# RevA.net
KiCad netlist of a schematic drawn in EAGLE
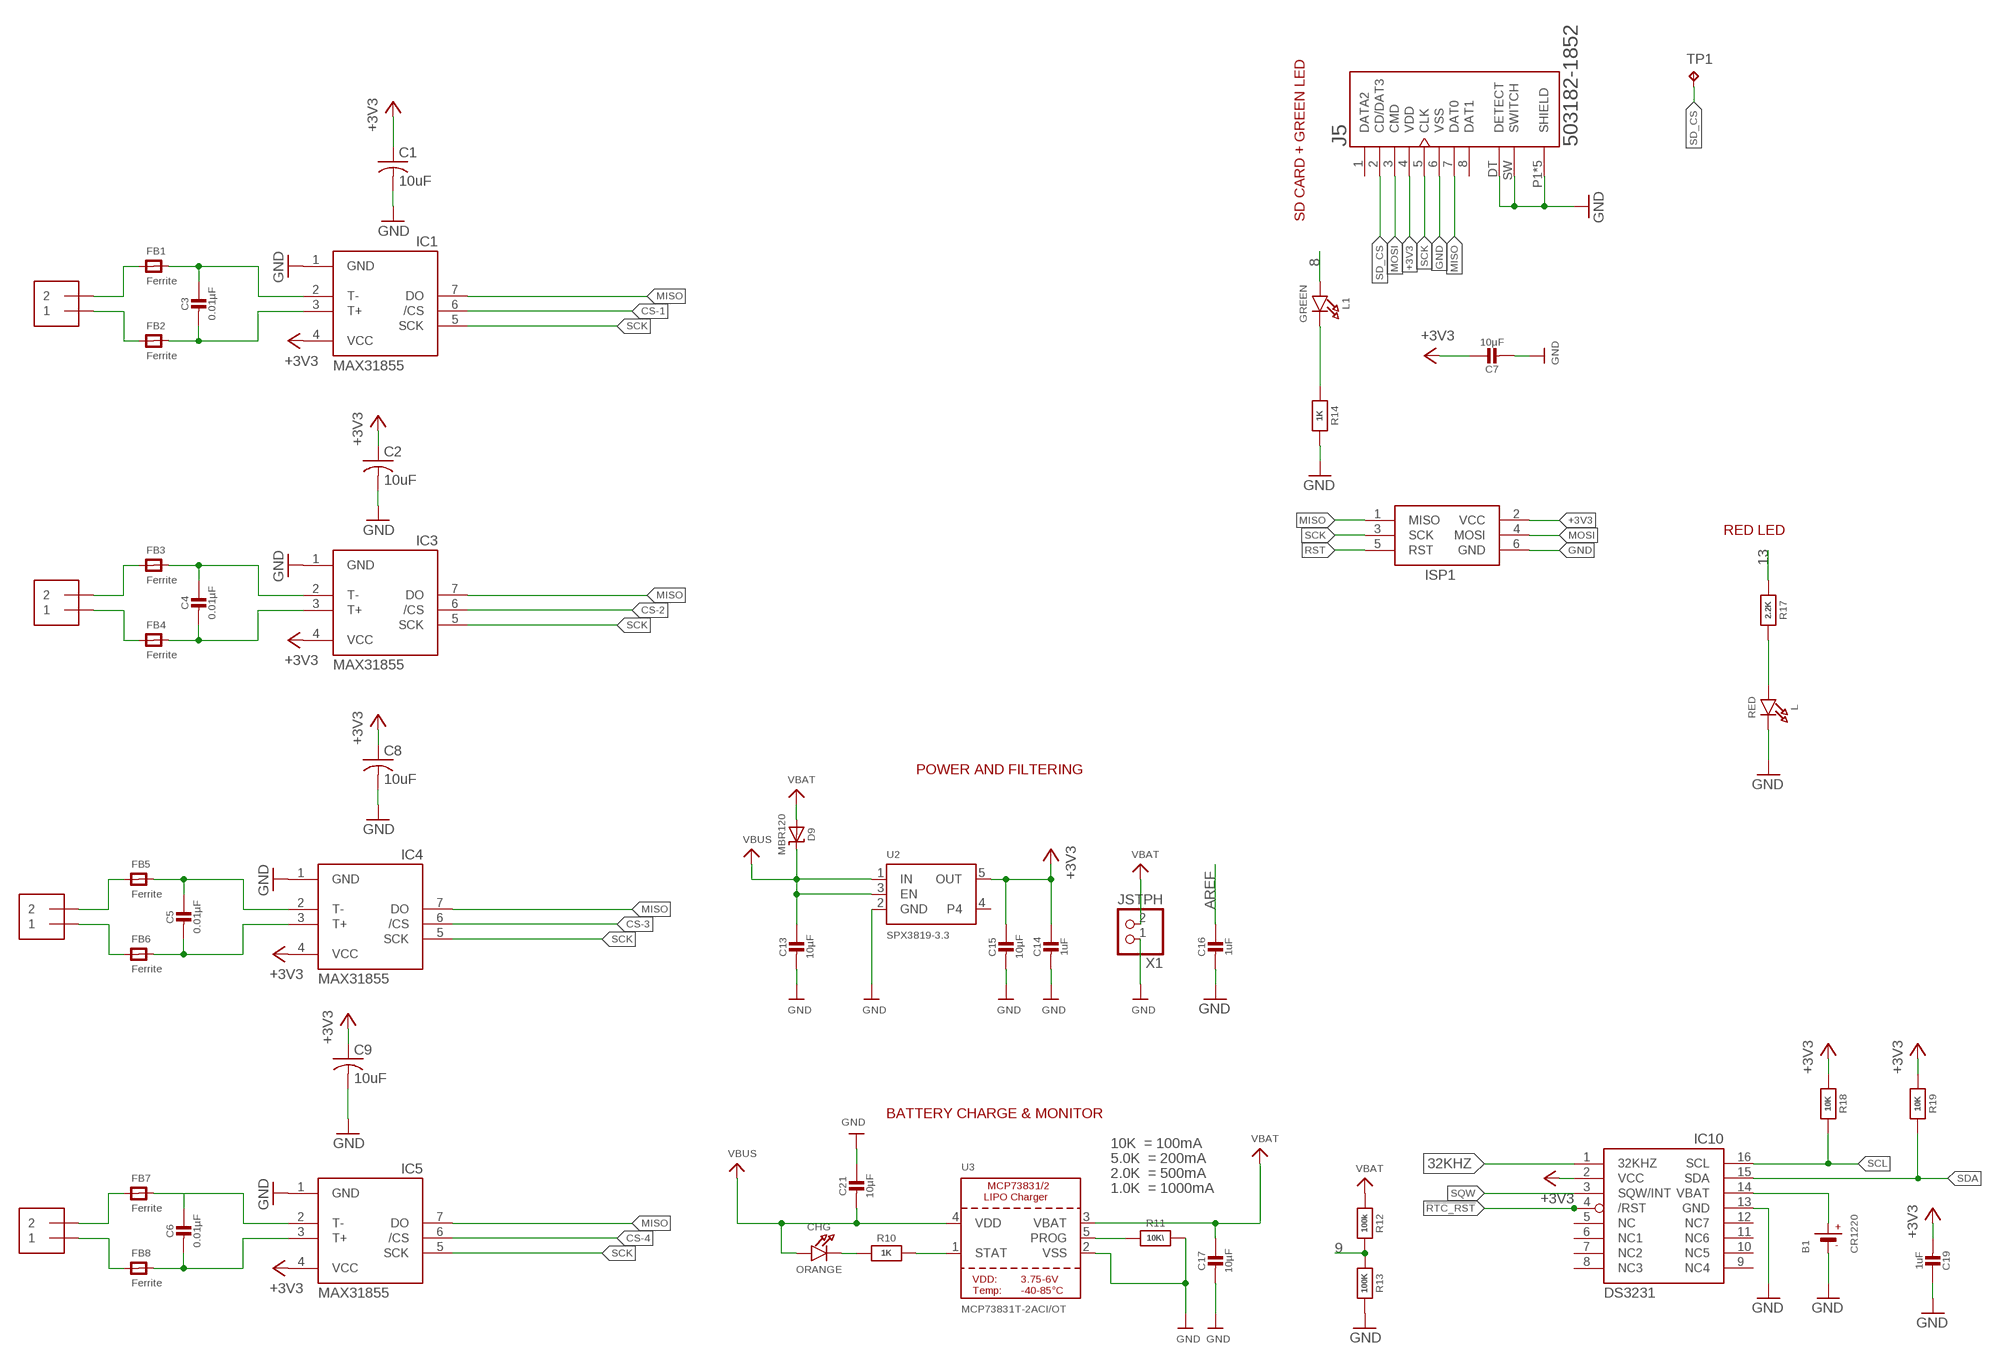
[diagram p0: schematic, sheet 1, part 1 of 2]
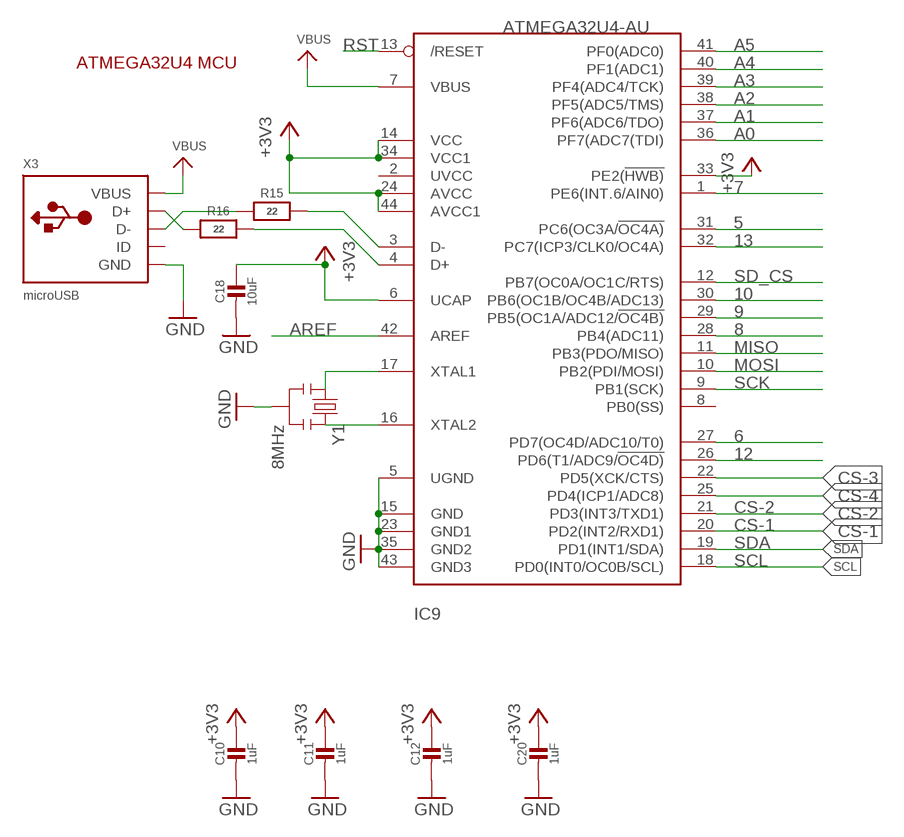
[diagram p1: schematic, sheet 1, part 2 of 2]

(export (version "E")
  (design (tool "Eeschema 10.0.6"))
  (components
    (comp (ref "B1")
      (value "CR1220")
      (footprint "eagle-import:CR1220")
      (libsource (lib "eagle-import") (part "BATTERYCR1220_SMT"))
    )
    (comp (ref "C1")
      (value "10uF")
      (footprint "eagle-import:C0805K")
      (libsource (lib "eagle-import") (part "C-USC0805K"))
    )
    (comp (ref "C2")
      (value "10uF")
      (footprint "eagle-import:C0805K")
      (libsource (lib "eagle-import") (part "C-USC0805K"))
    )
    (comp (ref "C3")
      (value "0.01µF")
      (footprint "eagle-import:_0805")
      (libsource (lib "eagle-import") (part "CAP_CERAMIC_0805"))
    )
    (comp (ref "C4")
      (value "0.01µF")
      (footprint "eagle-import:_0805")
      (libsource (lib "eagle-import") (part "CAP_CERAMIC_0805"))
    )
    (comp (ref "C5")
      (value "0.01µF")
      (footprint "eagle-import:_0805")
      (libsource (lib "eagle-import") (part "CAP_CERAMIC_0805"))
    )
    (comp (ref "C6")
      (value "0.01µF")
      (footprint "eagle-import:_0805")
      (libsource (lib "eagle-import") (part "CAP_CERAMIC_0805"))
    )
    (comp (ref "C7")
      (value "10µF")
      (footprint "eagle-import:0805-NO")
      (libsource (lib "eagle-import") (part "CAP_CERAMIC0805-NOOUTLINE"))
    )
    (comp (ref "C8")
      (value "10uF")
      (footprint "eagle-import:C0805K")
      (libsource (lib "eagle-import") (part "C-USC0805K"))
    )
    (comp (ref "C9")
      (value "10uF")
      (footprint "eagle-import:C0805K")
      (libsource (lib "eagle-import") (part "C-USC0805K"))
    )
    (comp (ref "C10")
      (value "1uF")
      (footprint "eagle-import:0603-NO")
      (libsource (lib "eagle-import") (part "CAP_CERAMIC0603_NO"))
    )
    (comp (ref "C11")
      (value "1uF")
      (footprint "eagle-import:0603-NO")
      (libsource (lib "eagle-import") (part "CAP_CERAMIC0603_NO"))
    )
    (comp (ref "C12")
      (value "1uF")
      (footprint "eagle-import:0603-NO")
      (libsource (lib "eagle-import") (part "CAP_CERAMIC0603_NO"))
    )
    (comp (ref "C13")
      (value "10µF")
      (footprint "eagle-import:0805-NO")
      (libsource (lib "eagle-import") (part "CAP_CERAMIC0805-NOOUTLINE"))
    )
    (comp (ref "C14")
      (value "1uF")
      (footprint "eagle-import:0603-NO")
      (libsource (lib "eagle-import") (part "CAP_CERAMIC0603_NO"))
    )
    (comp (ref "C15")
      (value "10µF")
      (footprint "eagle-import:0805-NO")
      (libsource (lib "eagle-import") (part "CAP_CERAMIC0805-NOOUTLINE"))
    )
    (comp (ref "C16")
      (value "1uF")
      (footprint "eagle-import:0603-NO")
      (libsource (lib "eagle-import") (part "CAP_CERAMIC0603_NO"))
    )
    (comp (ref "C17")
      (value "10µF")
      (footprint "eagle-import:0805-NO")
      (libsource (lib "eagle-import") (part "CAP_CERAMIC0805-NOOUTLINE"))
    )
    (comp (ref "C18")
      (value "10uF")
      (footprint "eagle-import:0805-NO")
      (libsource (lib "eagle-import") (part "CAP_CERAMIC0805-NOOUTLINE"))
    )
    (comp (ref "C19")
      (value "1uF")
      (footprint "eagle-import:0805-NO")
      (libsource (lib "eagle-import") (part "CAP_CERAMIC0805-NOOUTLINE"))
    )
    (comp (ref "C20")
      (value "1uF")
      (footprint "eagle-import:0603-NO")
      (libsource (lib "eagle-import") (part "CAP_CERAMIC0603_NO"))
    )
    (comp (ref "C21")
      (value "10µF")
      (footprint "eagle-import:0805-NO")
      (libsource (lib "eagle-import") (part "CAP_CERAMIC0805-NOOUTLINE"))
    )
    (comp (ref "CHG")
      (value "ORANGE")
      (footprint "eagle-import:CHIPLED_0805_NOOUTLINE")
      (libsource (lib "eagle-import") (part "LED0805_NOOUTLINE"))
    )
    (comp (ref "D9")
      (value "MBR120")
      (footprint "eagle-import:SOD-123")
      (libsource (lib "eagle-import") (part "DIODE-SCHOTTKYSOD-123"))
    )
    (comp (ref "FB1")
      (value "Ferrite")
      (footprint "eagle-import:_0805")
      (libsource (lib "eagle-import") (part "FERRITE_0805"))
    )
    (comp (ref "FB2")
      (value "Ferrite")
      (footprint "eagle-import:_0805")
      (libsource (lib "eagle-import") (part "FERRITE_0805"))
    )
    (comp (ref "FB3")
      (value "Ferrite")
      (footprint "eagle-import:_0805")
      (libsource (lib "eagle-import") (part "FERRITE_0805"))
    )
    (comp (ref "FB4")
      (value "Ferrite")
      (footprint "eagle-import:_0805")
      (libsource (lib "eagle-import") (part "FERRITE_0805"))
    )
    (comp (ref "FB5")
      (value "Ferrite")
      (footprint "eagle-import:_0805")
      (libsource (lib "eagle-import") (part "FERRITE_0805"))
    )
    (comp (ref "FB6")
      (value "Ferrite")
      (footprint "eagle-import:_0805")
      (libsource (lib "eagle-import") (part "FERRITE_0805"))
    )
    (comp (ref "FB7")
      (value "Ferrite")
      (footprint "eagle-import:_0805")
      (libsource (lib "eagle-import") (part "FERRITE_0805"))
    )
    (comp (ref "FB8")
      (value "Ferrite")
      (footprint "eagle-import:_0805")
      (libsource (lib "eagle-import") (part "FERRITE_0805"))
    )
    (comp (ref "IC1")
      (value "MAX31855")
      (footprint "eagle-import:SO08")
      (libsource (lib "eagle-import") (part "MAX6675"))
    )
    (comp (ref "IC3")
      (value "MAX31855")
      (footprint "eagle-import:SO08")
      (libsource (lib "eagle-import") (part "MAX6675"))
    )
    (comp (ref "IC4")
      (value "MAX31855")
      (footprint "eagle-import:SO08")
      (libsource (lib "eagle-import") (part "MAX6675"))
    )
    (comp (ref "IC5")
      (value "MAX31855")
      (footprint "eagle-import:SO08")
      (libsource (lib "eagle-import") (part "MAX6675"))
    )
    (comp (ref "IC9")
      (value "ATMEGA32U4-AU")
      (footprint "eagle-import:TQFP44")
      (libsource (lib "eagle-import") (part "ATMEGA32U4-AU"))
    )
    (comp (ref "IC10")
      (value "DS3231/SO")
      (footprint "eagle-import:SO16W")
      (libsource (lib "eagle-import") (part "DS3231/SO"))
    )
    (comp (ref "ISP1")
      (value "AVRISP-BOX")
      (footprint "eagle-import:AVRISP-BOX")
      (libsource (lib "eagle-import") (part "AVRISP-BOX"))
    )
    (comp (ref "J1")
      (value "1X2-3.5MM")
      (footprint "eagle-import:1X2-3.5MM")
      (libsource (lib "eagle-import") (part "1X2-3.5MM"))
    )
    (comp (ref "J2")
      (value "1X2-3.5MM")
      (footprint "eagle-import:1X2-3.5MM")
      (libsource (lib "eagle-import") (part "1X2-3.5MM"))
    )
    (comp (ref "J3")
      (value "1X2-3.5MM")
      (footprint "eagle-import:1X2-3.5MM")
      (libsource (lib "eagle-import") (part "1X2-3.5MM"))
    )
    (comp (ref "J4")
      (value "1X2-3.5MM")
      (footprint "eagle-import:1X2-3.5MM")
      (libsource (lib "eagle-import") (part "1X2-3.5MM"))
    )
    (comp (ref "J5")
      (value "503182-1852")
      (footprint "eagle-import:MOLEX_503182-1852")
      (fields
        (field (name "DIGI-KEY_PART_NUMBER") "WM12834CT-ND")
        (field (name "MF") "Molex")
        (field (name "MP") "5031821852")
      )
      (libsource (lib "eagle-import") (part "503182-1852"))
    )
    (comp (ref "L")
      (value "RED")
      (footprint "eagle-import:CHIPLED_0805_NOOUTLINE")
      (libsource (lib "eagle-import") (part "LED0805_NOOUTLINE"))
    )
    (comp (ref "L1")
      (value "GREEN")
      (footprint "eagle-import:CHIPLED_0805_NOOUTLINE")
      (libsource (lib "eagle-import") (part "LED0805_NOOUTLINE"))
    )
    (comp (ref "R10")
      (value "1K")
      (footprint "eagle-import:0603-NO")
      (libsource (lib "eagle-import") (part "RESISTOR_0603_NOOUT"))
    )
    (comp (ref "R11")
      (value "10K\\")
      (footprint "eagle-import:0603-NO")
      (libsource (lib "eagle-import") (part "RESISTOR_0603_NOOUT"))
    )
    (comp (ref "R12")
      (value "100k")
      (footprint "eagle-import:_0603MP")
      (libsource (lib "eagle-import") (part "RESISTOR_0603MP"))
    )
    (comp (ref "R13")
      (value "100K")
      (footprint "eagle-import:_0603MP")
      (libsource (lib "eagle-import") (part "RESISTOR_0603MP"))
    )
    (comp (ref "R14")
      (value "1K")
      (footprint "eagle-import:0603-NO")
      (libsource (lib "eagle-import") (part "RESISTOR_0603_NOOUT"))
    )
    (comp (ref "R15")
      (value "22")
      (footprint "eagle-import:0603-NO")
      (libsource (lib "eagle-import") (part "RESISTOR_0603_NOOUT"))
    )
    (comp (ref "R16")
      (value "22")
      (footprint "eagle-import:0603-NO")
      (libsource (lib "eagle-import") (part "RESISTOR_0603_NOOUT"))
    )
    (comp (ref "R17")
      (value "2.2K")
      (footprint "eagle-import:0603-NO")
      (libsource (lib "eagle-import") (part "RESISTOR_0603_NOOUT"))
    )
    (comp (ref "R18")
      (value "10K")
      (footprint "eagle-import:0805-NO")
      (libsource (lib "eagle-import") (part "RESISTOR0805_NOOUTLINE"))
    )
    (comp (ref "R19")
      (value "10K")
      (footprint "eagle-import:0805-NO")
      (libsource (lib "eagle-import") (part "RESISTOR0805_NOOUTLINE"))
    )
    (comp (ref "TP1")
      (value "TPPAD1-13")
      (footprint "eagle-import:P1-13")
      (libsource (lib "eagle-import") (part "TPPAD1-13"))
    )
    (comp (ref "U2")
      (value "SPX3819-3.3")
      (footprint "eagle-import:SOT23-5")
      (libsource (lib "eagle-import") (part "VREG_SOT23-5"))
    )
    (comp (ref "U3")
      (value "MCP73831T-2ACI/OT")
      (footprint "eagle-import:SOT23-5")
      (libsource (lib "eagle-import") (part "MCP73831/2"))
    )
    (comp (ref "X1")
      (value "JSTPH")
      (footprint "eagle-import:JSTPH2")
      (libsource (lib "eagle-import") (part "CON_JST_PH_2PIN"))
    )
    (comp (ref "X3")
      (value "microUSB")
      (footprint "eagle-import:4UCONN_20329_V2")
      (libsource (lib "eagle-import") (part "USB_MICRO_20329_V2"))
    )
    (comp (ref "Y1")
      (value "8MHz")
      (footprint "eagle-import:RESONATOR-SMD")
      (libsource (lib "eagle-import") (part "RESONATORSMD"))
    )
  )
  (nets
    (net (code "1") (name "+3V3") (class "Default")
      (node (ref "C1") (pin "1") (pinfunction "1_1") (pintype "passive"))
      (node (ref "C10") (pin "1") (pinfunction "1_1") (pintype "passive"))
      (node (ref "C11") (pin "1") (pinfunction "1_1") (pintype "passive"))
      (node (ref "C12") (pin "1") (pinfunction "1_1") (pintype "passive"))
      (node (ref "C14") (pin "1") (pinfunction "1_1") (pintype "passive"))
      (node (ref "C15") (pin "1") (pinfunction "1_1") (pintype "passive"))
      (node (ref "C18") (pin "1") (pinfunction "1_1") (pintype "passive"))
      (node (ref "C19") (pin "2") (pinfunction "2_2") (pintype "passive"))
      (node (ref "C2") (pin "1") (pinfunction "1_1") (pintype "passive"))
      (node (ref "C20") (pin "1") (pinfunction "1_1") (pintype "passive"))
      (node (ref "C7") (pin "1") (pinfunction "1_1") (pintype "passive"))
      (node (ref "C8") (pin "1") (pinfunction "1_1") (pintype "passive"))
      (node (ref "C9") (pin "1") (pinfunction "1_1") (pintype "passive"))
      (node (ref "IC1") (pin "4") (pinfunction "VCC_4") (pintype "power_in"))
      (node (ref "IC10") (pin "2") (pinfunction "VCC_2") (pintype "power_in"))
      (node (ref "IC3") (pin "4") (pinfunction "VCC_4") (pintype "power_in"))
      (node (ref "IC4") (pin "4") (pinfunction "VCC_4") (pintype "power_in"))
      (node (ref "IC5") (pin "4") (pinfunction "VCC_4") (pintype "power_in"))
      (node (ref "IC9") (pin "14") (pinfunction "VCC_14") (pintype "bidirectional"))
      (node (ref "IC9") (pin "24") (pinfunction "AVCC_24") (pintype "bidirectional"))
      (node (ref "IC9") (pin "33") (pinfunction "PE2(~{HWB})_33") (pintype "bidirectional"))
      (node (ref "IC9") (pin "34") (pinfunction "VCC1_34") (pintype "bidirectional"))
      (node (ref "IC9") (pin "44") (pinfunction "AVCC1_44") (pintype "bidirectional"))
      (node (ref "IC9") (pin "6") (pinfunction "UCAP_6") (pintype "bidirectional"))
      (node (ref "ISP1") (pin "2") (pinfunction "VCC_2") (pintype "power_in"))
      (node (ref "J5") (pin "4") (pinfunction "VDD_4") (pintype "power_in"))
      (node (ref "R18") (pin "1") (pinfunction "1_1") (pintype "passive"))
      (node (ref "R19") (pin "1") (pinfunction "1_1") (pintype "passive"))
      (node (ref "U2") (pin "5") (pinfunction "OUT_5") (pintype "power_in"))
    )
    (net (code "2") (name "/5") (class "Default")
      (node (ref "IC9") (pin "31") (pinfunction "PC6(OC3A/~{OC4A})_31") (pintype "bidirectional"))
    )
    (net (code "3") (name "/6") (class "Default")
      (node (ref "IC9") (pin "27") (pinfunction "PD7(OC4D/ADC10/T0)_27") (pintype "bidirectional"))
    )
    (net (code "4") (name "/7") (class "Default")
      (node (ref "IC9") (pin "1") (pinfunction "PE6(INT.6/AIN0)_1") (pintype "bidirectional"))
    )
    (net (code "5") (name "/8") (class "Default")
      (node (ref "IC9") (pin "28") (pinfunction "PB4(ADC11)_28") (pintype "bidirectional"))
      (node (ref "L1") (pin "A") (pinfunction "A_A") (pintype "passive"))
    )
    (net (code "6") (name "/9") (class "Default")
      (node (ref "IC9") (pin "29") (pinfunction "PB5(OC1A/ADC12/~{OC4B})_29") (pintype "bidirectional"))
      (node (ref "R12") (pin "2") (pinfunction "2_2") (pintype "passive"))
      (node (ref "R13") (pin "1") (pinfunction "1_1") (pintype "passive"))
    )
    (net (code "7") (name "/10") (class "Default")
      (node (ref "IC9") (pin "30") (pinfunction "PB6(OC1B/OC4B/ADC13)_30") (pintype "bidirectional"))
    )
    (net (code "8") (name "/12") (class "Default")
      (node (ref "IC9") (pin "26") (pinfunction "PD6(T1/ADC9/~{OC4D})_26") (pintype "bidirectional"))
    )
    (net (code "9") (name "/13") (class "Default")
      (node (ref "IC9") (pin "32") (pinfunction "PC7(ICP3/CLK0/OC4A)_32") (pintype "bidirectional"))
      (node (ref "R17") (pin "1") (pinfunction "1_1") (pintype "passive"))
    )
    (net (code "10") (name "/A0") (class "Default")
      (node (ref "IC9") (pin "36") (pinfunction "PF7(ADC7(TDI)_36") (pintype "bidirectional"))
    )
    (net (code "11") (name "/A1") (class "Default")
      (node (ref "IC9") (pin "37") (pinfunction "PF6(ADC6/TDO)_37") (pintype "bidirectional"))
    )
    (net (code "12") (name "/A2") (class "Default")
      (node (ref "IC9") (pin "38") (pinfunction "PF5(ADC5/TMS)_38") (pintype "bidirectional"))
    )
    (net (code "13") (name "/A3") (class "Default")
      (node (ref "IC9") (pin "39") (pinfunction "PF4(ADC4/TCK)_39") (pintype "bidirectional"))
    )
    (net (code "14") (name "/A4") (class "Default")
      (node (ref "IC9") (pin "40") (pinfunction "PF1(ADC1)_40") (pintype "bidirectional"))
    )
    (net (code "15") (name "/A5") (class "Default")
      (node (ref "IC9") (pin "41") (pinfunction "PF0(ADC0)_41") (pintype "bidirectional"))
    )
    (net (code "16") (name "/AREF") (class "Default")
      (node (ref "C16") (pin "1") (pinfunction "1_1") (pintype "passive"))
      (node (ref "IC9") (pin "42") (pinfunction "AREF_42") (pintype "bidirectional"))
    )
    (net (code "17") (name "/~{RTC_RST}") (class "Default")
      (node (ref "IC10") (pin "4") (pinfunction "/RST_4") (pintype "passive"))
    )
    (net (code "18") (name "32KHZ") (class "Default")
      (node (ref "IC10") (pin "1") (pinfunction "32KHZ_1") (pintype "output"))
    )
    (net (code "19") (name "CS-1") (class "Default")
      (node (ref "IC1") (pin "6") (pinfunction "/CS_6") (pintype "input"))
      (node (ref "IC9") (pin "20") (pinfunction "PD2(INT2/RXD1)_20") (pintype "bidirectional"))
    )
    (net (code "20") (name "CS-2") (class "Default")
      (node (ref "IC3") (pin "6") (pinfunction "/CS_6") (pintype "input"))
      (node (ref "IC9") (pin "21") (pinfunction "PD3(INT3/TXD1)_21") (pintype "bidirectional"))
    )
    (net (code "21") (name "CS-3") (class "Default")
      (node (ref "IC4") (pin "6") (pinfunction "/CS_6") (pintype "input"))
      (node (ref "IC9") (pin "22") (pinfunction "PD5(XCK/CTS)_22") (pintype "bidirectional"))
    )
    (net (code "22") (name "CS-4") (class "Default")
      (node (ref "IC5") (pin "6") (pinfunction "/CS_6") (pintype "input"))
      (node (ref "IC9") (pin "25") (pinfunction "PD4(ICP1/ADC8)_25") (pintype "bidirectional"))
    )
    (net (code "23") (name "GND") (class "Default")
      (node (ref "B1") (pin "-") (pinfunction "-_-") (pintype "passive"))
      (node (ref "C1") (pin "2") (pinfunction "2_2") (pintype "passive"))
      (node (ref "C10") (pin "2") (pinfunction "2_2") (pintype "passive"))
      (node (ref "C11") (pin "2") (pinfunction "2_2") (pintype "passive"))
      (node (ref "C12") (pin "2") (pinfunction "2_2") (pintype "passive"))
      (node (ref "C13") (pin "2") (pinfunction "2_2") (pintype "passive"))
      (node (ref "C14") (pin "2") (pinfunction "2_2") (pintype "passive"))
      (node (ref "C15") (pin "2") (pinfunction "2_2") (pintype "passive"))
      (node (ref "C16") (pin "2") (pinfunction "2_2") (pintype "passive"))
      (node (ref "C17") (pin "2") (pinfunction "2_2") (pintype "passive"))
      (node (ref "C18") (pin "2") (pinfunction "2_2") (pintype "passive"))
      (node (ref "C19") (pin "1") (pinfunction "1_1") (pintype "passive"))
      (node (ref "C2") (pin "2") (pinfunction "2_2") (pintype "passive"))
      (node (ref "C20") (pin "2") (pinfunction "2_2") (pintype "passive"))
      (node (ref "C21") (pin "1") (pinfunction "1_1") (pintype "passive"))
      (node (ref "C7") (pin "2") (pinfunction "2_2") (pintype "passive"))
      (node (ref "C8") (pin "2") (pinfunction "2_2") (pintype "passive"))
      (node (ref "C9") (pin "2") (pinfunction "2_2") (pintype "passive"))
      (node (ref "IC1") (pin "1") (pinfunction "GND_1") (pintype "power_in"))
      (node (ref "IC10") (pin "13") (pinfunction "GND_13") (pintype "power_in"))
      (node (ref "IC3") (pin "1") (pinfunction "GND_1") (pintype "power_in"))
      (node (ref "IC4") (pin "1") (pinfunction "GND_1") (pintype "power_in"))
      (node (ref "IC5") (pin "1") (pinfunction "GND_1") (pintype "power_in"))
      (node (ref "IC9") (pin "15") (pinfunction "GND_15") (pintype "bidirectional"))
      (node (ref "IC9") (pin "23") (pinfunction "GND1_23") (pintype "bidirectional"))
      (node (ref "IC9") (pin "35") (pinfunction "GND2_35") (pintype "bidirectional"))
      (node (ref "IC9") (pin "43") (pinfunction "GND3_43") (pintype "bidirectional"))
      (node (ref "IC9") (pin "5") (pinfunction "UGND_5") (pintype "bidirectional"))
      (node (ref "ISP1") (pin "6") (pinfunction "GND_6") (pintype "power_in"))
      (node (ref "J5") (pin "6") (pinfunction "VSS_6") (pintype "power_in"))
      (node (ref "J5") (pin "DT") (pinfunction "DETECT_DT") (pintype "bidirectional"))
      (node (ref "J5") (pin "P1") (pinfunction "SHIELD_P1") (pintype "passive"))
      (node (ref "J5") (pin "P2") (pinfunction "SHIELD_P2") (pintype "passive"))
      (node (ref "J5") (pin "P3") (pinfunction "SHIELD_P3") (pintype "passive"))
      (node (ref "J5") (pin "P4") (pinfunction "SHIELD_P4") (pintype "passive"))
      (node (ref "J5") (pin "P5") (pinfunction "SHIELD_P5") (pintype "passive"))
      (node (ref "J5") (pin "SW") (pinfunction "SWITCH_SW") (pintype "bidirectional"))
      (node (ref "L") (pin "C") (pinfunction "C_C") (pintype "passive"))
      (node (ref "R11") (pin "2") (pinfunction "2_2") (pintype "passive"))
      (node (ref "R13") (pin "2") (pinfunction "2_2") (pintype "passive"))
      (node (ref "R14") (pin "2") (pinfunction "2_2") (pintype "passive"))
      (node (ref "U2") (pin "2") (pinfunction "GND_2") (pintype "power_in"))
      (node (ref "U3") (pin "2") (pinfunction "VSS_2") (pintype "power_in"))
      (node (ref "X1") (pin "1") (pinfunction "1_1") (pintype "passive"))
      (node (ref "X3") (pin "BASE@1") (pinfunction "GND_BASE@1") (pintype "power_in"))
      (node (ref "X3") (pin "BASE@2") (pinfunction "GND_BASE@2") (pintype "power_in"))
      (node (ref "X3") (pin "GND") (pinfunction "GND_GND") (pintype "power_in"))
      (node (ref "X3") (pin "SPRT@1") (pinfunction "GND_SPRT@1") (pintype "power_in"))
      (node (ref "X3") (pin "SPRT@2") (pinfunction "GND_SPRT@2") (pintype "power_in"))
      (node (ref "X3") (pin "SPRT@3") (pinfunction "GND_SPRT@3") (pintype "power_in"))
      (node (ref "X3") (pin "SPRT@4") (pinfunction "GND_SPRT@4") (pintype "power_in"))
      (node (ref "Y1") (pin "2") (pinfunction "2_2") (pintype "passive"))
    )
    (net (code "24") (name "MISO") (class "Default")
      (node (ref "IC1") (pin "7") (pinfunction "DO_7") (pintype "output"))
      (node (ref "IC3") (pin "7") (pinfunction "DO_7") (pintype "output"))
      (node (ref "IC4") (pin "7") (pinfunction "DO_7") (pintype "output"))
      (node (ref "IC5") (pin "7") (pinfunction "DO_7") (pintype "output"))
      (node (ref "IC9") (pin "11") (pinfunction "PB3(PDO/MISO)_11") (pintype "bidirectional"))
      (node (ref "ISP1") (pin "1") (pinfunction "MISO_1") (pintype "input"))
      (node (ref "J5") (pin "7") (pinfunction "DAT0_7") (pintype "bidirectional"))
    )
    (net (code "25") (name "MOSI") (class "Default")
      (node (ref "IC9") (pin "10") (pinfunction "PB2(PDI/MOSI)_10") (pintype "bidirectional"))
      (node (ref "ISP1") (pin "4") (pinfunction "MOSI_4") (pintype "output"))
      (node (ref "J5") (pin "3") (pinfunction "CMD_3") (pintype "bidirectional"))
    )
    (net (code "26") (name "Net-(B1-+)") (class "Default")
      (node (ref "B1") (pin "+$1") (pinfunction "+_+$1") (pintype "passive"))
      (node (ref "IC10") (pin "14") (pinfunction "VBAT_14") (pintype "power_in"))
    )
    (net (code "27") (name "Net-(CHG-PadC)") (class "Default")
      (node (ref "CHG") (pin "C") (pinfunction "C_C") (pintype "passive"))
      (node (ref "R10") (pin "1") (pinfunction "1_1") (pintype "passive"))
    )
    (net (code "28") (name "Net-(FB1-P$1)") (class "Default")
      (node (ref "FB1") (pin "1") (pinfunction "P$1_1") (pintype "passive"))
      (node (ref "J1") (pin "2") (pinfunction "2_2") (pintype "passive"))
    )
    (net (code "29") (name "Net-(FB1-P$2)") (class "Default")
      (node (ref "C3") (pin "1") (pinfunction "1_1") (pintype "passive"))
      (node (ref "FB1") (pin "2") (pinfunction "P$2_2") (pintype "passive"))
      (node (ref "IC1") (pin "2") (pinfunction "T-_2") (pintype "input"))
    )
    (net (code "30") (name "Net-(FB2-P$1)") (class "Default")
      (node (ref "FB2") (pin "1") (pinfunction "P$1_1") (pintype "passive"))
      (node (ref "J1") (pin "1") (pinfunction "1_1") (pintype "passive"))
    )
    (net (code "31") (name "Net-(FB2-P$2)") (class "Default")
      (node (ref "C3") (pin "2") (pinfunction "2_2") (pintype "passive"))
      (node (ref "FB2") (pin "2") (pinfunction "P$2_2") (pintype "passive"))
      (node (ref "IC1") (pin "3") (pinfunction "T+_3") (pintype "input"))
    )
    (net (code "32") (name "Net-(FB3-P$1)") (class "Default")
      (node (ref "FB3") (pin "1") (pinfunction "P$1_1") (pintype "passive"))
      (node (ref "J2") (pin "2") (pinfunction "2_2") (pintype "passive"))
    )
    (net (code "33") (name "Net-(FB3-P$2)") (class "Default")
      (node (ref "C4") (pin "1") (pinfunction "1_1") (pintype "passive"))
      (node (ref "FB3") (pin "2") (pinfunction "P$2_2") (pintype "passive"))
      (node (ref "IC3") (pin "2") (pinfunction "T-_2") (pintype "input"))
    )
    (net (code "34") (name "Net-(FB4-P$1)") (class "Default")
      (node (ref "FB4") (pin "1") (pinfunction "P$1_1") (pintype "passive"))
      (node (ref "J2") (pin "1") (pinfunction "1_1") (pintype "passive"))
    )
    (net (code "35") (name "Net-(FB4-P$2)") (class "Default")
      (node (ref "C4") (pin "2") (pinfunction "2_2") (pintype "passive"))
      (node (ref "FB4") (pin "2") (pinfunction "P$2_2") (pintype "passive"))
      (node (ref "IC3") (pin "3") (pinfunction "T+_3") (pintype "input"))
    )
    (net (code "36") (name "Net-(FB5-P$1)") (class "Default")
      (node (ref "FB5") (pin "1") (pinfunction "P$1_1") (pintype "passive"))
      (node (ref "J3") (pin "2") (pinfunction "2_2") (pintype "passive"))
    )
    (net (code "37") (name "Net-(FB5-P$2)") (class "Default")
      (node (ref "C5") (pin "1") (pinfunction "1_1") (pintype "passive"))
      (node (ref "FB5") (pin "2") (pinfunction "P$2_2") (pintype "passive"))
      (node (ref "IC4") (pin "2") (pinfunction "T-_2") (pintype "input"))
    )
    (net (code "38") (name "Net-(FB6-P$1)") (class "Default")
      (node (ref "FB6") (pin "1") (pinfunction "P$1_1") (pintype "passive"))
      (node (ref "J3") (pin "1") (pinfunction "1_1") (pintype "passive"))
    )
    (net (code "39") (name "Net-(FB6-P$2)") (class "Default")
      (node (ref "C5") (pin "2") (pinfunction "2_2") (pintype "passive"))
      (node (ref "FB6") (pin "2") (pinfunction "P$2_2") (pintype "passive"))
      (node (ref "IC4") (pin "3") (pinfunction "T+_3") (pintype "input"))
    )
    (net (code "40") (name "Net-(FB7-P$1)") (class "Default")
      (node (ref "FB7") (pin "1") (pinfunction "P$1_1") (pintype "passive"))
      (node (ref "J4") (pin "2") (pinfunction "2_2") (pintype "passive"))
    )
    (net (code "41") (name "Net-(FB7-P$2)") (class "Default")
      (node (ref "C6") (pin "1") (pinfunction "1_1") (pintype "passive"))
      (node (ref "FB7") (pin "2") (pinfunction "P$2_2") (pintype "passive"))
      (node (ref "IC5") (pin "2") (pinfunction "T-_2") (pintype "input"))
    )
    (net (code "42") (name "Net-(FB8-P$1)") (class "Default")
      (node (ref "FB8") (pin "1") (pinfunction "P$1_1") (pintype "passive"))
      (node (ref "J4") (pin "1") (pinfunction "1_1") (pintype "passive"))
    )
    (net (code "43") (name "Net-(FB8-P$2)") (class "Default")
      (node (ref "C6") (pin "2") (pinfunction "2_2") (pintype "passive"))
      (node (ref "FB8") (pin "2") (pinfunction "P$2_2") (pintype "passive"))
      (node (ref "IC5") (pin "3") (pinfunction "T+_3") (pintype "input"))
    )
    (net (code "44") (name "Net-(IC9-D+)") (class "Default")
      (node (ref "IC9") (pin "4") (pinfunction "D+_4") (pintype "bidirectional"))
      (node (ref "R16") (pin "2") (pinfunction "2_2") (pintype "passive"))
    )
    (net (code "45") (name "Net-(IC9-D-)") (class "Default")
      (node (ref "IC9") (pin "3") (pinfunction "D-_3") (pintype "bidirectional"))
      (node (ref "R15") (pin "2") (pinfunction "2_2") (pintype "passive"))
    )
    (net (code "46") (name "Net-(IC9-XTAL1)") (class "Default")
      (node (ref "IC9") (pin "17") (pinfunction "XTAL1_17") (pintype "bidirectional"))
      (node (ref "Y1") (pin "1") (pinfunction "1_1") (pintype "passive"))
    )
    (net (code "47") (name "Net-(IC9-XTAL2)") (class "Default")
      (node (ref "IC9") (pin "16") (pinfunction "XTAL2_16") (pintype "bidirectional"))
      (node (ref "Y1") (pin "3") (pinfunction "3_3") (pintype "passive"))
    )
    (net (code "48") (name "Net-(L-PadA)") (class "Default")
      (node (ref "L") (pin "A") (pinfunction "A_A") (pintype "passive"))
      (node (ref "R17") (pin "2") (pinfunction "2_2") (pintype "passive"))
    )
    (net (code "49") (name "Net-(L1-PadC)") (class "Default")
      (node (ref "L1") (pin "C") (pinfunction "C_C") (pintype "passive"))
      (node (ref "R14") (pin "1") (pinfunction "1_1") (pintype "passive"))
    )
    (net (code "50") (name "Net-(R15-Pad1)") (class "Default")
      (node (ref "R15") (pin "1") (pinfunction "1_1") (pintype "passive"))
      (node (ref "X3") (pin "D-") (pinfunction "D-_D-") (pintype "bidirectional"))
    )
    (net (code "51") (name "Net-(R16-Pad1)") (class "Default")
      (node (ref "R16") (pin "1") (pinfunction "1_1") (pintype "passive"))
      (node (ref "X3") (pin "D+") (pinfunction "D+_D+") (pintype "bidirectional"))
    )
    (net (code "52") (name "Net-(U3-PROG)") (class "Default")
      (node (ref "R11") (pin "1") (pinfunction "1_1") (pintype "passive"))
      (node (ref "U3") (pin "5") (pinfunction "PROG_5") (pintype "input"))
    )
    (net (code "53") (name "Net-(U3-STAT)") (class "Default")
      (node (ref "R10") (pin "2") (pinfunction "2_2") (pintype "passive"))
      (node (ref "U3") (pin "1") (pinfunction "STAT_1") (pintype "output"))
    )
    (net (code "54") (name "RST") (class "Default")
      (node (ref "IC9") (pin "13") (pinfunction "/RESET_13") (pintype "bidirectional"))
      (node (ref "ISP1") (pin "5") (pinfunction "RST_5") (pintype "output"))
    )
    (net (code "55") (name "SCK") (class "Default")
      (node (ref "IC1") (pin "5") (pinfunction "SCK_5") (pintype "input"))
      (node (ref "IC3") (pin "5") (pinfunction "SCK_5") (pintype "input"))
      (node (ref "IC4") (pin "5") (pinfunction "SCK_5") (pintype "input"))
      (node (ref "IC5") (pin "5") (pinfunction "SCK_5") (pintype "input"))
      (node (ref "IC9") (pin "9") (pinfunction "PB1(SCK)_9") (pintype "bidirectional"))
      (node (ref "ISP1") (pin "3") (pinfunction "SCK_3") (pintype "output"))
      (node (ref "J5") (pin "5") (pinfunction "CLK_5") (pintype "bidirectional"))
    )
    (net (code "56") (name "SCL") (class "Default")
      (node (ref "IC10") (pin "16") (pinfunction "SCL_16") (pintype "bidirectional"))
      (node (ref "IC9") (pin "18") (pinfunction "PD0(INT0/OC0B/SCL)_18") (pintype "bidirectional"))
      (node (ref "R18") (pin "2") (pinfunction "2_2") (pintype "passive"))
    )
    (net (code "57") (name "SDA") (class "Default")
      (node (ref "IC10") (pin "15") (pinfunction "SDA_15") (pintype "bidirectional"))
      (node (ref "IC9") (pin "19") (pinfunction "PD1(INT1/SDA)_19") (pintype "bidirectional"))
      (node (ref "R19") (pin "2") (pinfunction "2_2") (pintype "passive"))
    )
    (net (code "58") (name "SD_CS") (class "Default")
      (node (ref "IC9") (pin "12") (pinfunction "PB7(OC0A/OC1C/RTS)_12") (pintype "bidirectional"))
      (node (ref "J5") (pin "2") (pinfunction "CD/DAT3_2") (pintype "bidirectional"))
      (node (ref "TP1") (pin "TP") (pinfunction "TP_TP") (pintype "input"))
    )
    (net (code "59") (name "SQW") (class "Default")
      (node (ref "IC10") (pin "3") (pinfunction "SQW/INT_3") (pintype "output"))
    )
    (net (code "60") (name "VBAT") (class "Default")
      (node (ref "C17") (pin "1") (pinfunction "1_1") (pintype "passive"))
      (node (ref "D9") (pin "A") (pinfunction "A_A") (pintype "passive"))
      (node (ref "R12") (pin "1") (pinfunction "1_1") (pintype "passive"))
      (node (ref "U3") (pin "3") (pinfunction "VBAT_3") (pintype "power_in"))
      (node (ref "X1") (pin "2") (pinfunction "2_2") (pintype "passive"))
    )
    (net (code "61") (name "VBUS") (class "Default")
      (node (ref "C13") (pin "1") (pinfunction "1_1") (pintype "passive"))
      (node (ref "C21") (pin "2") (pinfunction "2_2") (pintype "passive"))
      (node (ref "CHG") (pin "A") (pinfunction "A_A") (pintype "passive"))
      (node (ref "D9") (pin "C") (pinfunction "C_C") (pintype "passive"))
      (node (ref "IC9") (pin "7") (pinfunction "VBUS_7") (pintype "bidirectional"))
      (node (ref "U2") (pin "1") (pinfunction "IN_1") (pintype "power_in"))
      (node (ref "U2") (pin "3") (pinfunction "EN_3") (pintype "input"))
      (node (ref "U3") (pin "4") (pinfunction "VDD_4") (pintype "power_in"))
      (node (ref "X3") (pin "VBUS") (pinfunction "VBUS_VBUS") (pintype "power_in"))
    )
    (net (code "62") (name "unconnected-(IC9-PB0(SS)-Pad8)") (class "Default")
      (node (ref "IC9") (pin "8") (pinfunction "PB0(SS)_8") (pintype "bidirectional"))
    )
    (net (code "63") (name "unconnected-(IC9-UVCC-Pad2)") (class "Default")
      (node (ref "IC9") (pin "2") (pinfunction "UVCC_2") (pintype "bidirectional"))
    )
    (net (code "64") (name "unconnected-(IC10-NC-Pad5)") (class "Default")
      (node (ref "IC10") (pin "5") (pinfunction "NC_5") (pintype "no_connect"))
    )
    (net (code "65") (name "unconnected-(IC10-NC1-Pad6)") (class "Default")
      (node (ref "IC10") (pin "6") (pinfunction "NC1_6") (pintype "no_connect"))
    )
    (net (code "66") (name "unconnected-(IC10-NC2-Pad7)") (class "Default")
      (node (ref "IC10") (pin "7") (pinfunction "NC2_7") (pintype "no_connect"))
    )
    (net (code "67") (name "unconnected-(IC10-NC3-Pad8)") (class "Default")
      (node (ref "IC10") (pin "8") (pinfunction "NC3_8") (pintype "no_connect"))
    )
    (net (code "68") (name "unconnected-(IC10-NC4-Pad9)") (class "Default")
      (node (ref "IC10") (pin "9") (pinfunction "NC4_9") (pintype "no_connect"))
    )
    (net (code "69") (name "unconnected-(IC10-NC5-Pad10)") (class "Default")
      (node (ref "IC10") (pin "10") (pinfunction "NC5_10") (pintype "no_connect"))
    )
    (net (code "70") (name "unconnected-(IC10-NC6-Pad11)") (class "Default")
      (node (ref "IC10") (pin "11") (pinfunction "NC6_11") (pintype "no_connect"))
    )
    (net (code "71") (name "unconnected-(IC10-NC7-Pad12)") (class "Default")
      (node (ref "IC10") (pin "12") (pinfunction "NC7_12") (pintype "no_connect"))
    )
    (net (code "72") (name "unconnected-(J5-DAT1-Pad8)") (class "Default")
      (node (ref "J5") (pin "8") (pinfunction "DAT1_8") (pintype "bidirectional"))
    )
    (net (code "73") (name "unconnected-(J5-DATA2-Pad1)") (class "Default")
      (node (ref "J5") (pin "1") (pinfunction "DATA2_1") (pintype "bidirectional"))
    )
    (net (code "74") (name "unconnected-(U2-P4-Pad4)") (class "Default")
      (node (ref "U2") (pin "4") (pinfunction "P4_4") (pintype "bidirectional"))
    )
    (net (code "75") (name "unconnected-(X3-PadID)") (class "Default")
      (node (ref "X3") (pin "ID") (pinfunction "ID_ID") (pintype "bidirectional"))
    )
  )
)
